# LED_driver.net
KiCad netlist of a schematic drawn in EAGLE
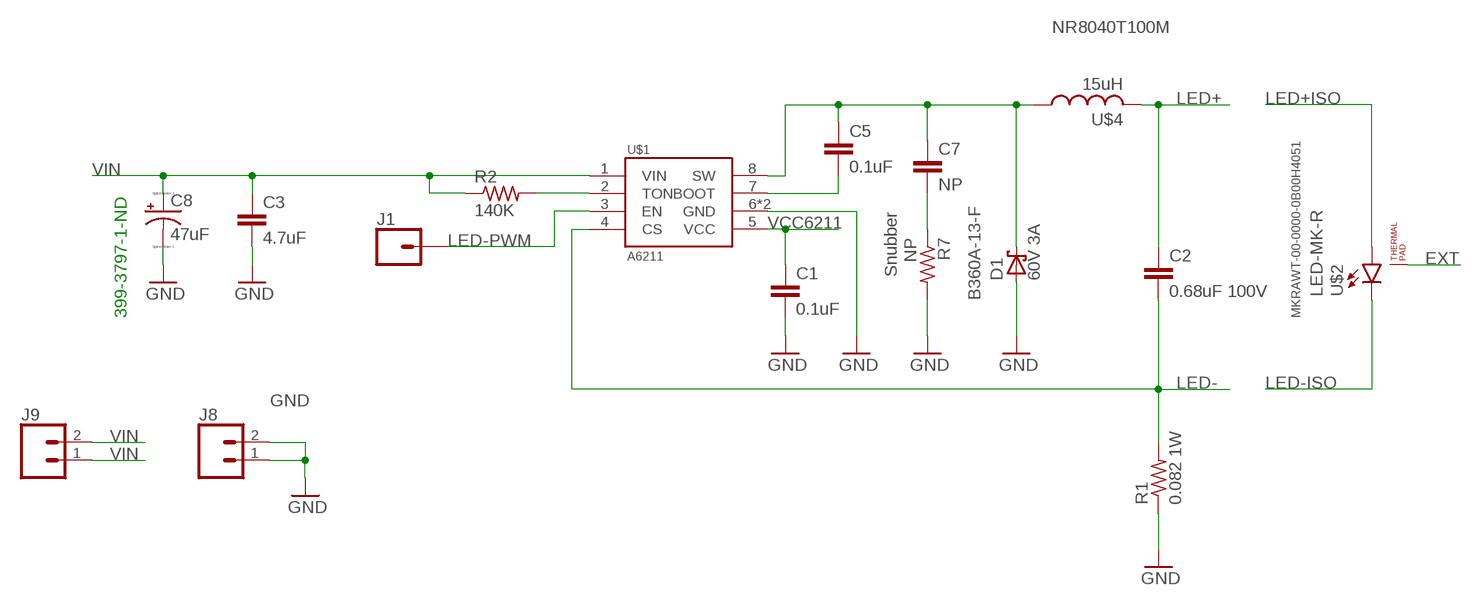
[diagram p0: schematic, sheet 1]

(export (version "E")
  (design (tool "Eeschema 10.0.6"))
  (components
    (comp (ref "C1")
      (value "0.1uF")
      (footprint "eagle-import:C0603")
      (libsource (lib "eagle-import") (part "resistor_C-EUC0603"))
    )
    (comp (ref "C2")
      (value "0.68uF 100V")
      (footprint "eagle-import:C0805")
      (libsource (lib "eagle-import") (part "resistor_C-EUC0805"))
    )
    (comp (ref "C3")
      (value "4.7uF")
      (footprint "eagle-import:C0603")
      (libsource (lib "eagle-import") (part "C-EUC0603"))
    )
    (comp (ref "C5")
      (value "0.1uF")
      (footprint "eagle-import:C0603")
      (libsource (lib "eagle-import") (part "resistor_C-EUC0603"))
    )
    (comp (ref "C7")
      (value "NP")
      (footprint "eagle-import:C0603")
      (libsource (lib "eagle-import") (part "resistor_C-EUC0603"))
    )
    (comp (ref "C8")
      (value "47uF")
      (footprint "eagle-import:CTAN(7.30_4.30MM)")
      (libsource (lib "eagle-import") (part "C-TANTALUM(10UF_150UF)"))
    )
    (comp (ref "D1")
      (value "60V 3A")
      (footprint "eagle-import:SMA")
      (libsource (lib "eagle-import") (part "DIODE-SCHOTTKYSMA"))
    )
    (comp (ref "J1")
      (value "CONN_01")
      (footprint "eagle-import:1X01")
      (libsource (lib "eagle-import") (part "CONN_01"))
    )
    (comp (ref "J8")
      (value "CONN_021X02_NO_SILK")
      (footprint "eagle-import:1X02_NO_SILK")
      (libsource (lib "eagle-import") (part "CONN_021X02_NO_SILK"))
    )
    (comp (ref "J9")
      (value "CONN_021X02_NO_SILK")
      (footprint "eagle-import:1X02_NO_SILK")
      (libsource (lib "eagle-import") (part "CONN_021X02_NO_SILK"))
    )
    (comp (ref "R1")
      (value "0.082 1W")
      (footprint "eagle-import:R2512")
      (libsource (lib "eagle-import") (part "R-US_R2512"))
    )
    (comp (ref "R2")
      (value "140K")
      (footprint "eagle-import:R0603")
      (libsource (lib "eagle-import") (part "R-US_R0603"))
    )
    (comp (ref "R7")
      (value "NP")
      (footprint "eagle-import:R1206")
      (libsource (lib "eagle-import") (part "R-US_R1206"))
    )
    (comp (ref "U$1")
      (value "A6211")
      (footprint "eagle-import:SOIC8N-LJ")
      (libsource (lib "eagle-import") (part "A6211"))
    )
    (comp (ref "U$2")
      (value "LED-MK-R")
      (footprint "eagle-import:MK-R")
      (libsource (lib "eagle-import") (part "LED-MK-R"))
    )
    (comp (ref "U$4")
      (value "15uH")
      (footprint "eagle-import:HCMA1305")
      (libsource (lib "eagle-import") (part "HCMA1305"))
    )
  )
  (nets
    (net (code "1") (name "/EXT") (class "Default")
      (node (ref "U$2") (pin "EXP") (pinfunction "THERMAL_EXP") (pintype "bidirectional"))
    )
    (net (code "2") (name "/LED+") (class "Default")
      (node (ref "C2") (pin "1") (pinfunction "1_1") (pintype "passive"))
      (node (ref "U$4") (pin "P$2") (pinfunction "2_P$2") (pintype "passive"))
    )
    (net (code "3") (name "/LED+ISO") (class "Default")
      (node (ref "U$2") (pin "A") (pinfunction "A_A") (pintype "passive"))
    )
    (net (code "4") (name "/LED-") (class "Default")
      (node (ref "C2") (pin "2") (pinfunction "2_2") (pintype "passive"))
      (node (ref "R1") (pin "2") (pinfunction "2_2") (pintype "passive"))
      (node (ref "U$1") (pin "4") (pinfunction "CS_4") (pintype "bidirectional"))
    )
    (net (code "5") (name "/LED-ISO") (class "Default")
      (node (ref "U$2") (pin "C") (pinfunction "C_C") (pintype "passive"))
    )
    (net (code "6") (name "/LED-PWM") (class "Default")
      (node (ref "J1") (pin "1") (pinfunction "1_1") (pintype "passive"))
      (node (ref "U$1") (pin "3") (pinfunction "EN_3") (pintype "bidirectional"))
    )
    (net (code "7") (name "/VCC6211") (class "Default")
      (node (ref "C1") (pin "1") (pinfunction "1_1") (pintype "passive"))
      (node (ref "U$1") (pin "5") (pinfunction "VCC_5") (pintype "bidirectional"))
    )
    (net (code "8") (name "/VIN") (class "Default")
      (node (ref "C3") (pin "1") (pinfunction "1_1") (pintype "passive"))
      (node (ref "C8") (pin "+") (pinfunction "+_+") (pintype "passive"))
      (node (ref "J9") (pin "1") (pinfunction "1_1") (pintype "passive"))
      (node (ref "J9") (pin "2") (pinfunction "2_2") (pintype "passive"))
      (node (ref "R2") (pin "1") (pinfunction "1_1") (pintype "passive"))
      (node (ref "U$1") (pin "1") (pinfunction "VIN_1") (pintype "bidirectional"))
    )
    (net (code "9") (name "GND") (class "Default")
      (node (ref "C1") (pin "2") (pinfunction "2_2") (pintype "passive"))
      (node (ref "C3") (pin "2") (pinfunction "2_2") (pintype "passive"))
      (node (ref "C8") (pin "-") (pinfunction "-_-") (pintype "passive"))
      (node (ref "D1") (pin "A") (pinfunction "A_A") (pintype "passive"))
      (node (ref "J8") (pin "1") (pinfunction "1_1") (pintype "passive"))
      (node (ref "J8") (pin "2") (pinfunction "2_2") (pintype "passive"))
      (node (ref "R1") (pin "1") (pinfunction "1_1") (pintype "passive"))
      (node (ref "R7") (pin "2") (pinfunction "2_2") (pintype "passive"))
      (node (ref "U$1") (pin "6") (pinfunction "GND_6") (pintype "bidirectional"))
      (node (ref "U$1") (pin "PAD") (pinfunction "GND_PAD") (pintype "bidirectional"))
    )
    (net (code "10") (name "Net-(C7-Pad2)") (class "Default")
      (node (ref "C7") (pin "2") (pinfunction "2_2") (pintype "passive"))
      (node (ref "R7") (pin "1") (pinfunction "1_1") (pintype "passive"))
    )
    (net (code "11") (name "Net-(U$1-BOOT)") (class "Default")
      (node (ref "C5") (pin "2") (pinfunction "2_2") (pintype "passive"))
      (node (ref "U$1") (pin "7") (pinfunction "BOOT_7") (pintype "bidirectional"))
    )
    (net (code "12") (name "Net-(U$1-SW)") (class "Default")
      (node (ref "C5") (pin "1") (pinfunction "1_1") (pintype "passive"))
      (node (ref "C7") (pin "1") (pinfunction "1_1") (pintype "passive"))
      (node (ref "D1") (pin "C") (pinfunction "C_C") (pintype "passive"))
      (node (ref "U$1") (pin "8") (pinfunction "SW_8") (pintype "bidirectional"))
      (node (ref "U$4") (pin "P$1") (pinfunction "1_P$1") (pintype "passive"))
    )
    (net (code "13") (name "Net-(U$1-TON)") (class "Default")
      (node (ref "R2") (pin "2") (pinfunction "2_2") (pintype "passive"))
      (node (ref "U$1") (pin "2") (pinfunction "TON_2") (pintype "bidirectional"))
    )
  )
)
